# HB_Driver2.net
KiCad netlist of a schematic drawn in Altium Designer
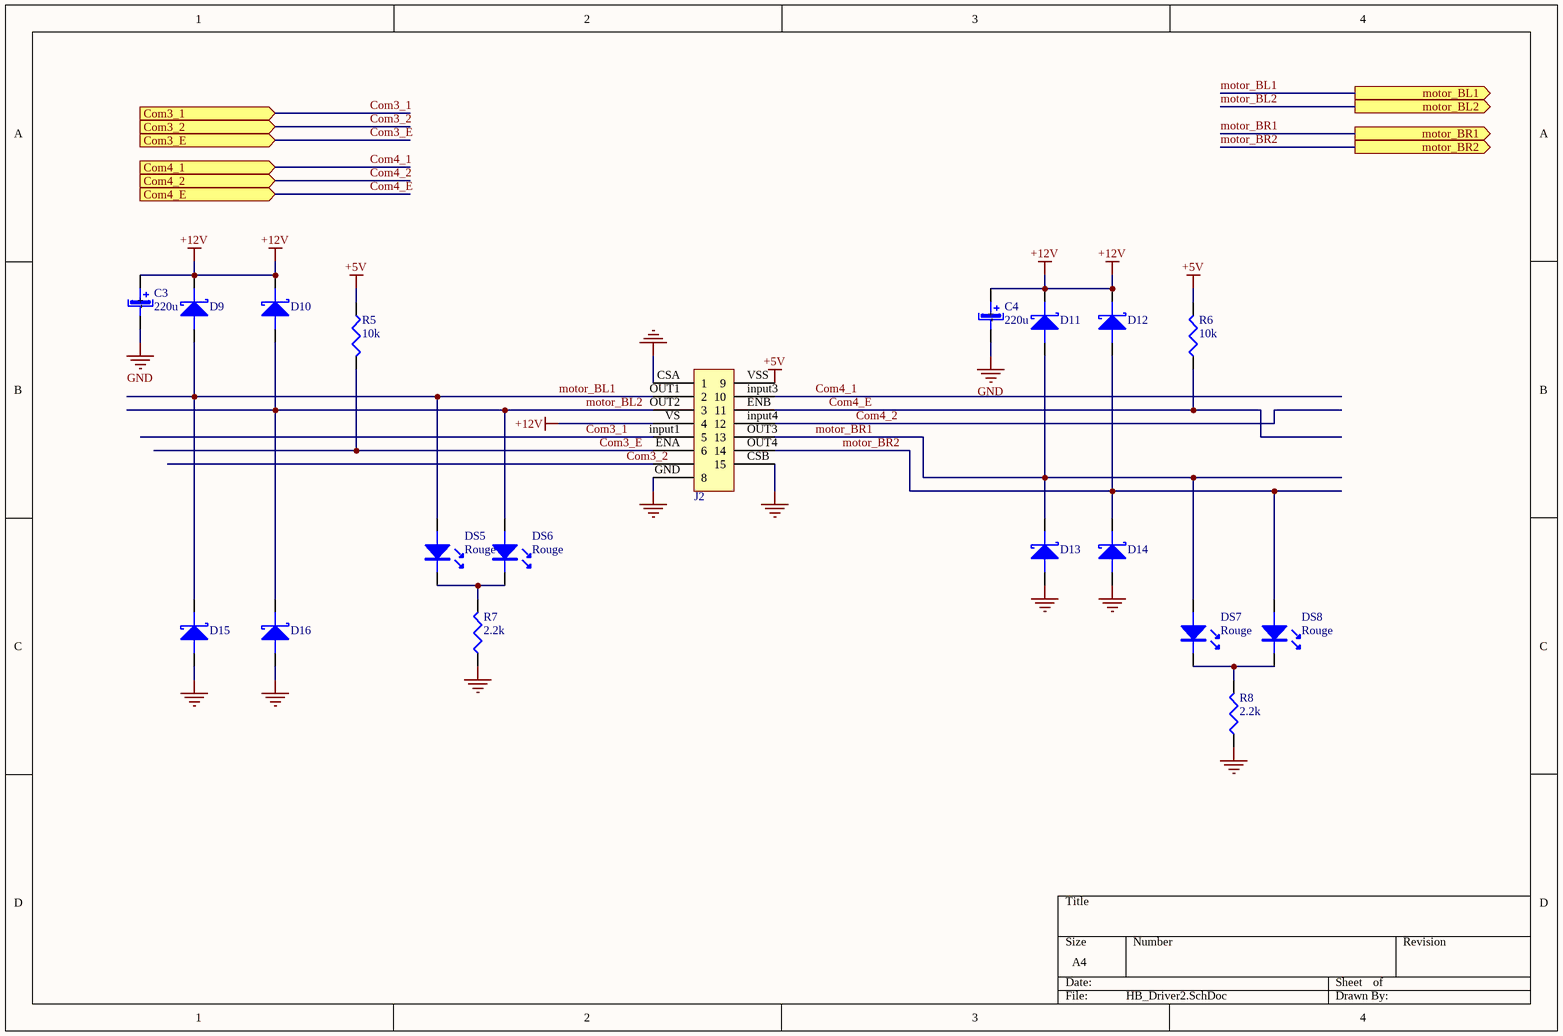
[diagram p0: HB_Driver2.SchDoc]

(export (version "E")
  (design (tool "Eeschema 10.0.6"))
  (components
    (comp (ref "C3")
      (value "220u")
      (footprint "CAPAE0810X700N")
      (description "Condensateur polatisé")
      (fields (field (name "Comment") "Cap_220u") (field (name "DESIGNER") "ECAM 2004"))
      (libsource (lib "HBLib") (part "Cap_220u"))
    )
    (comp (ref "C4")
      (value "220u")
      (footprint "CAPAE0810X700N")
      (description "Condensateur polatisé")
      (fields (field (name "Comment") "Cap_220u") (field (name "DESIGNER") "ECAM 2004"))
      (libsource (lib "HBLib") (part "Cap_220u"))
    )
    (comp (ref "D9")
      (value "Diode Schottky")
      (footprint "SOD-123")
      (fields (field (name "DESIGNER") "ECAM 2005"))
      (libsource (lib "HBLib") (part "Diode Schottky"))
    )
    (comp (ref "D10")
      (value "Diode Schottky")
      (footprint "SOD-123")
      (fields (field (name "DESIGNER") "ECAM 2005"))
      (libsource (lib "HBLib") (part "Diode Schottky"))
    )
    (comp (ref "D11")
      (value "Diode Schottky")
      (footprint "SOD-123")
      (fields (field (name "DESIGNER") "ECAM 2005"))
      (libsource (lib "HBLib") (part "Diode Schottky"))
    )
    (comp (ref "D12")
      (value "Diode Schottky")
      (footprint "SOD-123")
      (fields (field (name "DESIGNER") "ECAM 2005"))
      (libsource (lib "HBLib") (part "Diode Schottky"))
    )
    (comp (ref "D13")
      (value "Diode Schottky")
      (footprint "SOD-123")
      (fields (field (name "DESIGNER") "ECAM 2005"))
      (libsource (lib "HBLib") (part "Diode Schottky"))
    )
    (comp (ref "D14")
      (value "Diode Schottky")
      (footprint "SOD-123")
      (fields (field (name "DESIGNER") "ECAM 2005"))
      (libsource (lib "HBLib") (part "Diode Schottky"))
    )
    (comp (ref "D15")
      (value "Diode Schottky")
      (footprint "SOD-123")
      (fields (field (name "DESIGNER") "ECAM 2005"))
      (libsource (lib "HBLib") (part "Diode Schottky"))
    )
    (comp (ref "D16")
      (value "Diode Schottky")
      (footprint "SOD-123")
      (fields (field (name "DESIGNER") "ECAM 2005"))
      (libsource (lib "HBLib") (part "Diode Schottky"))
    )
    (comp (ref "DS5")
      (value "LED")
      (footprint "3.5X2.8X1.9")
      (fields (field (name "COLOR") "Rouge") (field (name "DESIGNER") "ECAM 2004"))
      (libsource (lib "HBLib") (part "LED"))
    )
    (comp (ref "DS6")
      (value "LED")
      (footprint "3.5X2.8X1.9")
      (fields (field (name "COLOR") "Rouge") (field (name "DESIGNER") "ECAM 2004"))
      (libsource (lib "HBLib") (part "LED"))
    )
    (comp (ref "DS7")
      (value "LED")
      (footprint "3.5X2.8X1.9")
      (fields (field (name "COLOR") "Rouge") (field (name "DESIGNER") "ECAM 2004"))
      (libsource (lib "HBLib") (part "LED"))
    )
    (comp (ref "DS8")
      (value "LED")
      (footprint "3.5X2.8X1.9")
      (fields (field (name "COLOR") "Rouge") (field (name "DESIGNER") "ECAM 2004"))
      (libsource (lib "HBLib") (part "LED"))
    )
    (comp (ref "J2")
      (value "L298")
      (footprint "MultiWatt15")
      (description "Connecteur")
      (fields (field (name "DESIGNER") "ECAM 2004"))
      (libsource (lib "HBLib") (part "L298"))
    )
    (comp (ref "R5")
      (value "10k")
      (footprint "6-0805_L")
      (description "Résistance standard")
      (fields (field (name "Comment") "Res_10k") (field (name "DESIGNER") "ECAM 2005"))
      (libsource (lib "HBLib") (part "Res_10k"))
    )
    (comp (ref "R6")
      (value "10k")
      (footprint "6-0805_L")
      (description "Résistance standard")
      (fields (field (name "Comment") "Res_10k") (field (name "DESIGNER") "ECAM 2005"))
      (libsource (lib "HBLib") (part "Res_10k"))
    )
    (comp (ref "R7")
      (value "2.2k")
      (footprint "6-0805_L")
      (description "Résistance standard")
      (fields (field (name "Comment") "Res_2.2k") (field (name "DESIGNER") "ECAM 2005"))
      (libsource (lib "HBLib") (part "Res_2.2k"))
    )
    (comp (ref "R8")
      (value "2.2k")
      (footprint "6-0805_L")
      (description "Résistance standard")
      (fields (field (name "Comment") "Res_2.2k") (field (name "DESIGNER") "ECAM 2005"))
      (libsource (lib "HBLib") (part "Res_2.2k"))
    )
  )
  (nets
    (net (code "1") (name "+5V") (class "Default")
      (node (ref "J2") (pin "VSS") (pinfunction "9_VSS") (pintype "passive"))
      (node (ref "R5") (pin "1") (pinfunction "1_1") (pintype "passive"))
      (node (ref "R6") (pin "2") (pinfunction "2_2") (pintype "passive"))
    )
    (net (code "2") (name "+12V") (class "Default")
      (node (ref "C3") (pin "POS") (pinfunction "+_POS") (pintype "passive"))
      (node (ref "C4") (pin "POS") (pinfunction "+_POS") (pintype "passive"))
      (node (ref "D10") (pin "1") (pinfunction "K_1") (pintype "passive"))
      (node (ref "D11") (pin "1") (pinfunction "K_1") (pintype "passive"))
      (node (ref "D12") (pin "1") (pinfunction "K_1") (pintype "passive"))
      (node (ref "D9") (pin "1") (pinfunction "K_1") (pintype "passive"))
      (node (ref "J2") (pin "VS") (pinfunction "4_VS") (pintype "passive"))
    )
    (net (code "3") (name "/Com3_1") (class "Default")
      (node (ref "J2") (pin "input1") (pinfunction "5_input1") (pintype "passive"))
    )
    (net (code "4") (name "/Com3_2") (class "Default")
      (node (ref "J2") (pin "input2") (pinfunction "7_input2") (pintype "passive"))
    )
    (net (code "5") (name "/Com3_E") (class "Default")
      (node (ref "J2") (pin "ENA") (pinfunction "6_ENA") (pintype "passive"))
      (node (ref "R5") (pin "2") (pinfunction "2_2") (pintype "passive"))
    )
    (net (code "6") (name "/Com4_1") (class "Default")
      (node (ref "J2") (pin "input3") (pinfunction "10_input3") (pintype "passive"))
    )
    (net (code "7") (name "/Com4_2") (class "Default")
      (node (ref "J2") (pin "input4") (pinfunction "12_input4") (pintype "passive"))
    )
    (net (code "8") (name "/Com4_E") (class "Default")
      (node (ref "J2") (pin "ENB") (pinfunction "11_ENB") (pintype "passive"))
      (node (ref "R6") (pin "1") (pinfunction "1_1") (pintype "passive"))
    )
    (net (code "9") (name "/motor_BL1") (class "Default")
      (node (ref "D15") (pin "1") (pinfunction "K_1") (pintype "passive"))
      (node (ref "D9") (pin "2") (pinfunction "A_2") (pintype "passive"))
      (node (ref "DS5") (pin "1") (pinfunction "A_1") (pintype "passive"))
      (node (ref "J2") (pin "OUT1") (pinfunction "2_OUT1") (pintype "passive"))
    )
    (net (code "10") (name "/motor_BL2") (class "Default")
      (node (ref "D10") (pin "2") (pinfunction "A_2") (pintype "passive"))
      (node (ref "D16") (pin "1") (pinfunction "K_1") (pintype "passive"))
      (node (ref "DS6") (pin "1") (pinfunction "A_1") (pintype "passive"))
      (node (ref "J2") (pin "OUT2") (pinfunction "3_OUT2") (pintype "passive"))
    )
    (net (code "11") (name "/motor_BR1") (class "Default")
      (node (ref "D11") (pin "2") (pinfunction "A_2") (pintype "passive"))
      (node (ref "D13") (pin "1") (pinfunction "K_1") (pintype "passive"))
      (node (ref "DS7") (pin "1") (pinfunction "A_1") (pintype "passive"))
      (node (ref "J2") (pin "OUT3") (pinfunction "13_OUT3") (pintype "passive"))
    )
    (net (code "12") (name "/motor_BR2") (class "Default")
      (node (ref "D12") (pin "2") (pinfunction "A_2") (pintype "passive"))
      (node (ref "D14") (pin "1") (pinfunction "K_1") (pintype "passive"))
      (node (ref "DS8") (pin "1") (pinfunction "A_1") (pintype "passive"))
      (node (ref "J2") (pin "OUT4") (pinfunction "14_OUT4") (pintype "passive"))
    )
    (net (code "13") (name "GND") (class "Default")
      (node (ref "C3") (pin "NEG") (pinfunction "-_NEG") (pintype "passive"))
      (node (ref "C4") (pin "NEG") (pinfunction "-_NEG") (pintype "passive"))
      (node (ref "D13") (pin "2") (pinfunction "A_2") (pintype "passive"))
      (node (ref "D14") (pin "2") (pinfunction "A_2") (pintype "passive"))
      (node (ref "D15") (pin "2") (pinfunction "A_2") (pintype "passive"))
      (node (ref "D16") (pin "2") (pinfunction "A_2") (pintype "passive"))
      (node (ref "J2") (pin "CSA") (pinfunction "1_CSA") (pintype "passive"))
      (node (ref "J2") (pin "CSB") (pinfunction "15_CSB") (pintype "passive"))
      (node (ref "J2") (pin "GND") (pinfunction "8_GND") (pintype "passive"))
      (node (ref "R7") (pin "1") (pinfunction "1_1") (pintype "passive"))
      (node (ref "R8") (pin "1") (pinfunction "1_1") (pintype "passive"))
    )
    (net (code "14") (name "Net-(DS5-K)") (class "Default")
      (node (ref "DS5") (pin "2") (pinfunction "K_2") (pintype "passive"))
      (node (ref "DS6") (pin "2") (pinfunction "K_2") (pintype "passive"))
      (node (ref "R7") (pin "2") (pinfunction "2_2") (pintype "passive"))
    )
    (net (code "15") (name "Net-(DS7-K)") (class "Default")
      (node (ref "DS7") (pin "2") (pinfunction "K_2") (pintype "passive"))
      (node (ref "DS8") (pin "2") (pinfunction "K_2") (pintype "passive"))
      (node (ref "R8") (pin "2") (pinfunction "2_2") (pintype "passive"))
    )
  )
)
